# ESP32_RGB_Controller.net
KiCad netlist of a schematic drawn in Altium Designer
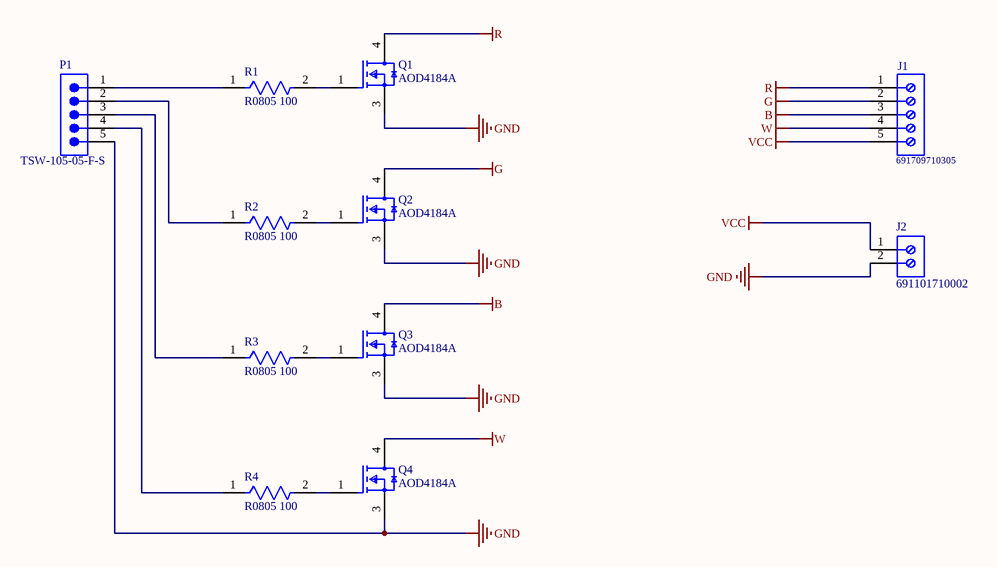
[diagram p0: ESP32_RGB_Controller.SchDoc]

(export (version "E")
  (design (tool "Eeschema 10.0.6"))
  (components
    (comp (ref "J1")
      (value "691709710305")
      (footprint "691709710305")
      (description "Serie 7097 - 5.00 mm Horizontal Entry SMT with Pressure Clamp WR-TBL, 5 pin")
      (fields (field (name "MANUFACTURER") "Wurth Elektronik") (field (name "PUBLISHER") "WurthElektronik"))
      (libsource (lib "Altium Content Vault") (part "WE-CN-1P-F-TB5"))
    )
    (comp (ref "J2")
      (value "691101710002")
      (footprint "691101710002")
      (description "Series 101 - 5.00 mm Horizontal Entry Modular with Pressure Clamp WR-TBL, 2 pin")
      (fields (field (name "MANUFACTURER") "Wurth Elektronik") (field (name "PUBLISHER") "WurthElektronik"))
      (libsource (lib "Altium Content Vault") (part "WE-CN-1P-F-TB2"))
    )
    (comp (ref "P1")
      (value "TSW-105-05-F-S")
      (footprint "SMTC-TSW-105-05-X-S")
      (description "0.025\" SQ Post Header, Through-hole, Vertical, -55 to 125 degC, 2.54 mm Pitch, 5-Pin, Male, RoHS")
      (fields (field (name "MANUFACTURER") "Samtec"))
      (libsource (lib "Altium Content Vault") (part "SMTC-TSW-105-05-X-S"))
    )
    (comp (ref "Q1")
      (value "AOD4184A")
      (footprint "FP-TO252-MFG")
      (description "MOSFET N-CH 40V 50A TO252")
      (libsource (lib "Altium Content Vault") (part "eaf820099600a16e7148a0c70285cb7"))
    )
    (comp (ref "Q2")
      (value "AOD4184A")
      (footprint "FP-TO252-MFG")
      (description "MOSFET N-CH 40V 50A TO252")
      (libsource (lib "Altium Content Vault") (part "eaf820099600a16e7148a0c70285cb7"))
    )
    (comp (ref "Q3")
      (value "AOD4184A")
      (footprint "FP-TO252-MFG")
      (description "MOSFET N-CH 40V 50A TO252")
      (libsource (lib "Altium Content Vault") (part "eaf820099600a16e7148a0c70285cb7"))
    )
    (comp (ref "Q4")
      (value "AOD4184A")
      (footprint "FP-TO252-MFG")
      (description "MOSFET N-CH 40V 50A TO252")
      (libsource (lib "Altium Content Vault") (part "eaf820099600a16e7148a0c70285cb7"))
    )
    (comp (ref "R1")
      (value "R0805 100")
      (footprint "FP-SR0805-MFG")
      (description "RES 100 OHM 1% 1/2W 0805")
      (fields
        (field (name "TOLERANCE") "0.01")
        (field (name "OCTOPART") "https://octopart.com/sr0805fr-47100rl-yageo-91478093")
      )
      (libsource (lib "Altium Content Vault") (part "1029c3af85768c4190bb7ad29bc67b5"))
    )
    (comp (ref "R2")
      (value "R0805 100")
      (footprint "FP-SR0805-MFG")
      (description "RES 100 OHM 1% 1/2W 0805")
      (fields
        (field (name "TOLERANCE") "0.01")
        (field (name "OCTOPART") "https://octopart.com/sr0805fr-47100rl-yageo-91478093")
      )
      (libsource (lib "Altium Content Vault") (part "1029c3af85768c4190bb7ad29bc67b5"))
    )
    (comp (ref "R3")
      (value "R0805 100")
      (footprint "FP-SR0805-MFG")
      (description "RES 100 OHM 1% 1/2W 0805")
      (fields
        (field (name "TOLERANCE") "0.01")
        (field (name "OCTOPART") "https://octopart.com/sr0805fr-47100rl-yageo-91478093")
      )
      (libsource (lib "Altium Content Vault") (part "1029c3af85768c4190bb7ad29bc67b5"))
    )
    (comp (ref "R4")
      (value "R0805 100")
      (footprint "FP-SR0805-MFG")
      (description "RES 100 OHM 1% 1/2W 0805")
      (fields
        (field (name "TOLERANCE") "0.01")
        (field (name "OCTOPART") "https://octopart.com/sr0805fr-47100rl-yageo-91478093")
      )
      (libsource (lib "Altium Content Vault") (part "1029c3af85768c4190bb7ad29bc67b5"))
    )
  )
  (nets
    (net (code "1") (name "B") (class "Default")
      (node (ref "J1") (pin "3") (pinfunction "3_3") (pintype "passive"))
      (node (ref "Q3") (pin "4") (pinfunction "D_4") (pintype "passive"))
    )
    (net (code "2") (name "G") (class "Default")
      (node (ref "J1") (pin "2") (pinfunction "2_2") (pintype "passive"))
      (node (ref "Q2") (pin "4") (pinfunction "D_4") (pintype "passive"))
    )
    (net (code "3") (name "GND") (class "Default")
      (node (ref "J2") (pin "2") (pinfunction "2_2") (pintype "passive"))
      (node (ref "P1") (pin "5") (pinfunction "5_5") (pintype "passive"))
      (node (ref "Q1") (pin "3") (pinfunction "S_3") (pintype "passive"))
      (node (ref "Q2") (pin "3") (pinfunction "S_3") (pintype "passive"))
      (node (ref "Q3") (pin "3") (pinfunction "S_3") (pintype "passive"))
      (node (ref "Q4") (pin "3") (pinfunction "S_3") (pintype "passive"))
    )
    (net (code "4") (name "Net-(P1-Pad1)") (class "Default")
      (node (ref "P1") (pin "1") (pinfunction "1_1") (pintype "passive"))
      (node (ref "R1") (pin "1") (pinfunction "1_1") (pintype "passive"))
    )
    (net (code "5") (name "Net-(P1-Pad2)") (class "Default")
      (node (ref "P1") (pin "2") (pinfunction "2_2") (pintype "passive"))
      (node (ref "R2") (pin "1") (pinfunction "1_1") (pintype "passive"))
    )
    (net (code "6") (name "Net-(P1-Pad3)") (class "Default")
      (node (ref "P1") (pin "3") (pinfunction "3_3") (pintype "passive"))
      (node (ref "R3") (pin "1") (pinfunction "1_1") (pintype "passive"))
    )
    (net (code "7") (name "Net-(P1-Pad4)") (class "Default")
      (node (ref "P1") (pin "4") (pinfunction "4_4") (pintype "passive"))
      (node (ref "R4") (pin "1") (pinfunction "1_1") (pintype "passive"))
    )
    (net (code "8") (name "Net-(Q1-G)") (class "Default")
      (node (ref "Q1") (pin "1") (pinfunction "G_1") (pintype "passive"))
      (node (ref "R1") (pin "2") (pinfunction "2_2") (pintype "passive"))
    )
    (net (code "9") (name "Net-(Q2-G)") (class "Default")
      (node (ref "Q2") (pin "1") (pinfunction "G_1") (pintype "passive"))
      (node (ref "R2") (pin "2") (pinfunction "2_2") (pintype "passive"))
    )
    (net (code "10") (name "Net-(Q3-G)") (class "Default")
      (node (ref "Q3") (pin "1") (pinfunction "G_1") (pintype "passive"))
      (node (ref "R3") (pin "2") (pinfunction "2_2") (pintype "passive"))
    )
    (net (code "11") (name "Net-(Q4-G)") (class "Default")
      (node (ref "Q4") (pin "1") (pinfunction "G_1") (pintype "passive"))
      (node (ref "R4") (pin "2") (pinfunction "2_2") (pintype "passive"))
    )
    (net (code "12") (name "R") (class "Default")
      (node (ref "J1") (pin "1") (pinfunction "1_1") (pintype "passive"))
      (node (ref "Q1") (pin "4") (pinfunction "D_4") (pintype "passive"))
    )
    (net (code "13") (name "VCC") (class "Default")
      (node (ref "J1") (pin "5") (pinfunction "5_5") (pintype "passive"))
      (node (ref "J2") (pin "1") (pinfunction "1_1") (pintype "passive"))
    )
    (net (code "14") (name "W") (class "Default")
      (node (ref "J1") (pin "4") (pinfunction "4_4") (pintype "passive"))
      (node (ref "Q4") (pin "4") (pinfunction "D_4") (pintype "passive"))
    )
  )
)
